# SATA-Modular-Backplane.net
KiCad netlist of a schematic drawn in Altium Designer
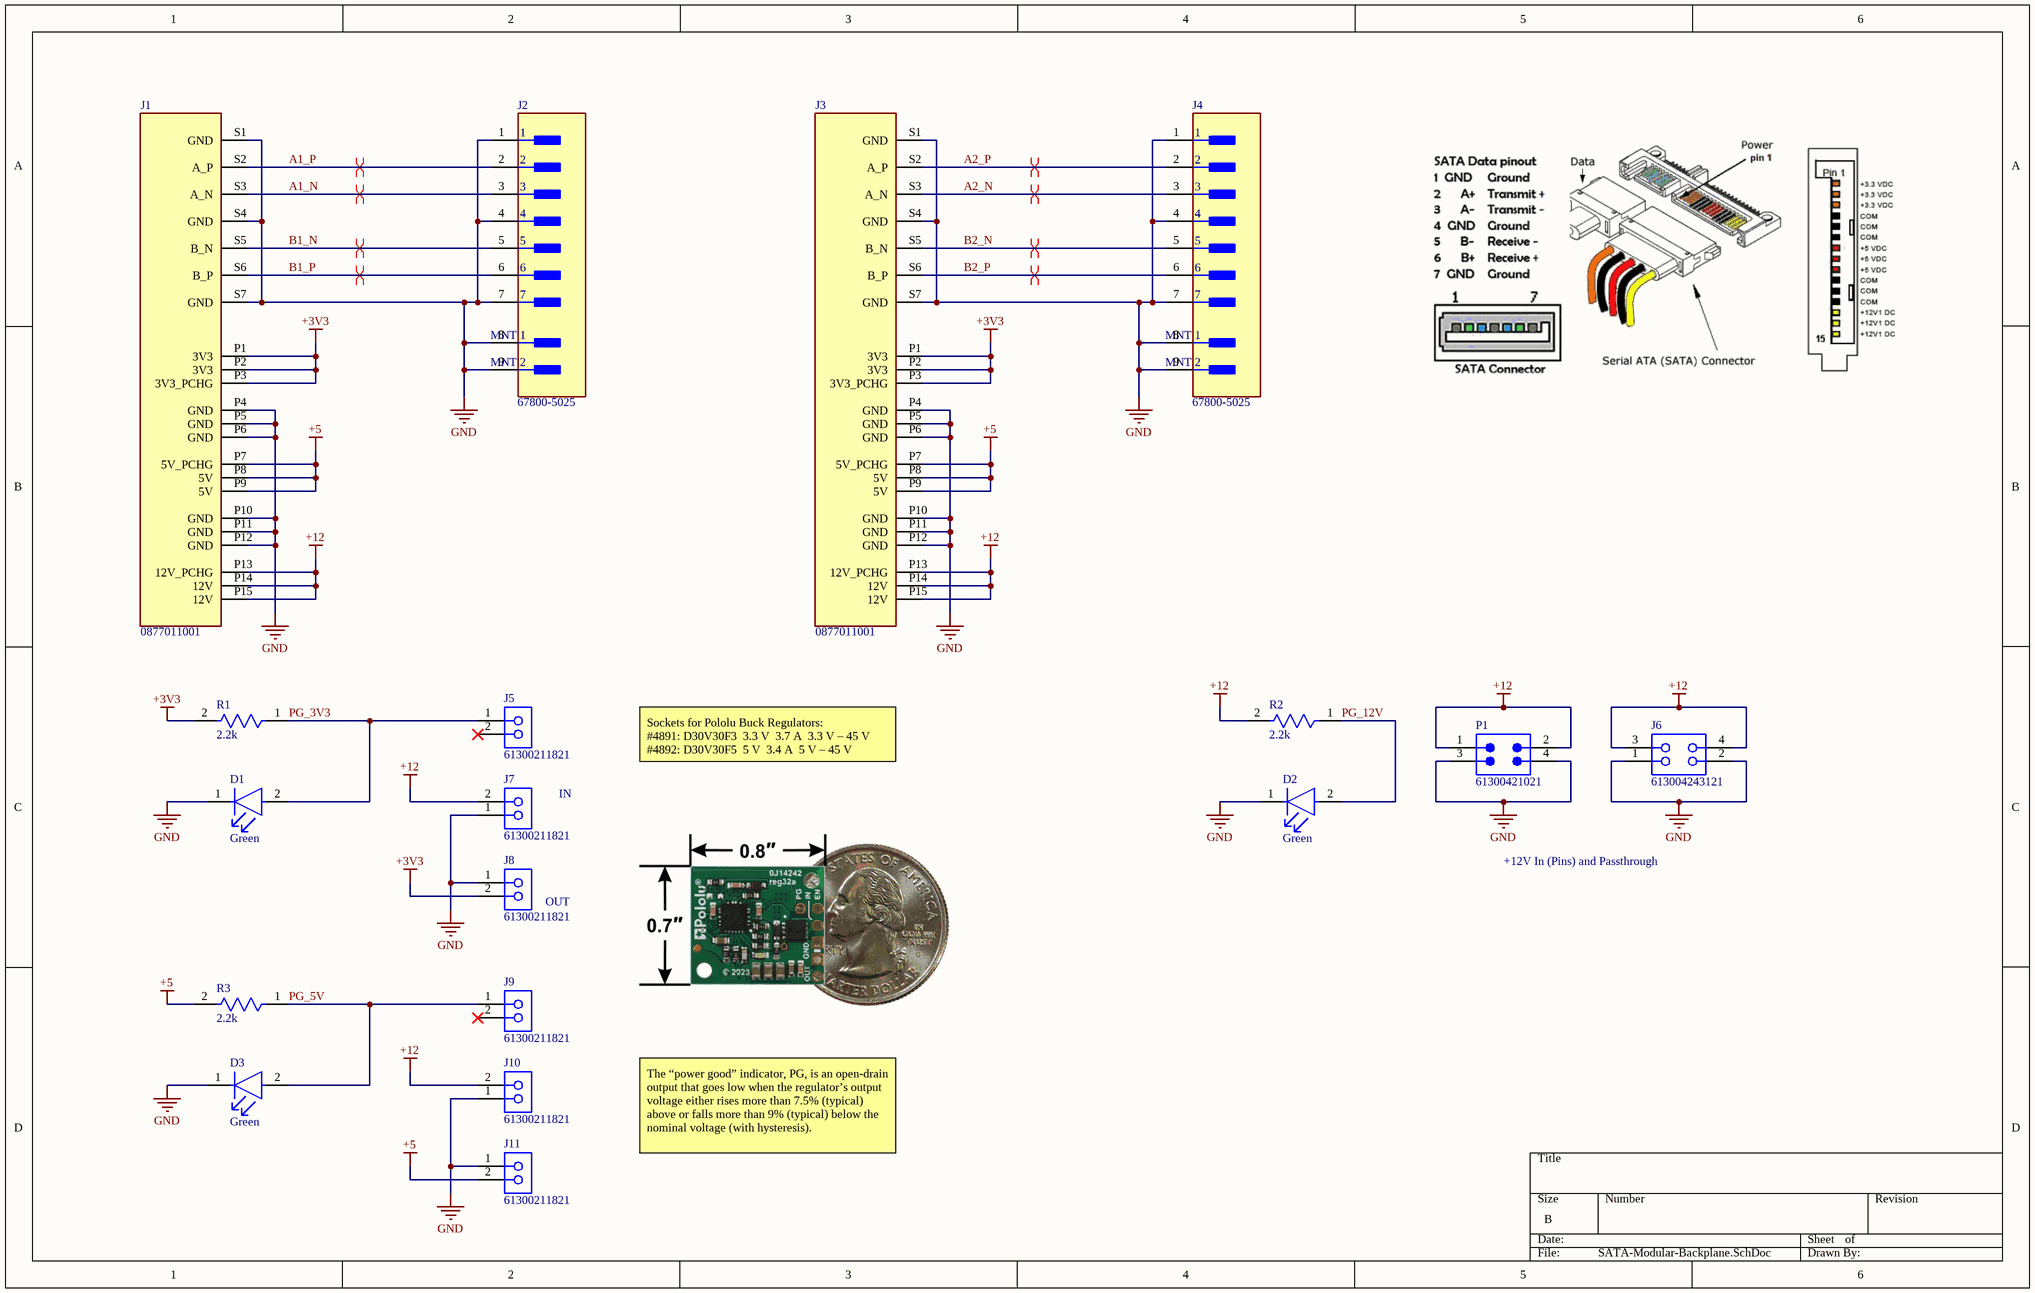
[diagram p0: SATA-Modular-Backplane.SchDoc]

(export (version "E")
  (design (tool "Eeschema 10.0.6"))
  (components
    (comp (ref "D1")
      (value "Green")
      (footprint "FP-LTST-C170GKT-MFG")
      (description "LED GREEN CLEAR SMD")
      (fields (field (name "VOLTAGE") "5V"))
      (libsource (lib "Altium Content Vault") (part "8706943c75ba83719d021d2fdc84c58"))
    )
    (comp (ref "D2")
      (value "Green")
      (footprint "FP-LTST-C170GKT-MFG")
      (description "LED GREEN CLEAR SMD")
      (fields (field (name "VOLTAGE") "5V"))
      (libsource (lib "Altium Content Vault") (part "8706943c75ba83719d021d2fdc84c58"))
    )
    (comp (ref "D3")
      (value "Green")
      (footprint "FP-LTST-C170GKT-MFG")
      (description "LED GREEN CLEAR SMD")
      (fields (field (name "VOLTAGE") "5V"))
      (libsource (lib "Altium Content Vault") (part "8706943c75ba83719d021d2fdc84c58"))
    )
    (comp (ref "J1")
      (value "0877011001")
      (footprint "SamacSys:0877011001")
      (description "I/O Connectors SATA COMBO HOST REC VT PFIT")
      (libsource (lib "Simple-Six-SATA-Backplane-Special") (part "0877011001"))
    )
    (comp (ref "J2")
      (value "67800-5025")
      (footprint "FP-67800-5025-MFG")
      (description "CONN SATA HEADER 7POS SLD SMD")
      (libsource (lib "Altium Content Vault") (part "989b0b90c267bc36b7e102b24762a7b"))
    )
    (comp (ref "J3")
      (value "0877011001")
      (footprint "SamacSys:0877011001")
      (description "I/O Connectors SATA COMBO HOST REC VT PFIT")
      (libsource (lib "Simple-Six-SATA-Backplane-Special") (part "0877011001"))
    )
    (comp (ref "J4")
      (value "67800-5025")
      (footprint "FP-67800-5025-MFG")
      (description "CONN SATA HEADER 7POS SLD SMD")
      (libsource (lib "Altium Content Vault") (part "989b0b90c267bc36b7e102b24762a7b"))
    )
    (comp (ref "J5")
      (value "61300211821")
      (footprint "61300211821")
      (libsource (lib "Altium Content Vault") (part "Header_Female_1R_02P"))
    )
    (comp (ref "J6")
      (value "613004243121")
      (footprint "613004243121")
      (libsource (lib "Altium Content Vault") (part "Header_Female_2R_04P"))
    )
    (comp (ref "J7")
      (value "61300211821")
      (footprint "61300211821")
      (libsource (lib "Altium Content Vault") (part "Header_Female_1R_02P"))
    )
    (comp (ref "J8")
      (value "61300211821")
      (footprint "61300211821")
      (libsource (lib "Altium Content Vault") (part "Header_Female_1R_02P"))
    )
    (comp (ref "J9")
      (value "61300211821")
      (footprint "61300211821")
      (libsource (lib "Altium Content Vault") (part "Header_Female_1R_02P"))
    )
    (comp (ref "J10")
      (value "61300211821")
      (footprint "61300211821")
      (libsource (lib "Altium Content Vault") (part "Header_Female_1R_02P"))
    )
    (comp (ref "J11")
      (value "61300211821")
      (footprint "61300211821")
      (libsource (lib "Altium Content Vault") (part "Header_Female_1R_02P"))
    )
    (comp (ref "P1")
      (value "61300421021")
      (footprint "61300421021")
      (libsource (lib "Altium Content Vault") (part "Header_Male_2R_04P"))
    )
    (comp (ref "R1")
      (value "2.2k")
      (footprint "FP-CRCW0805-e3-IPC_B")
      (description "RES Thick Film, 2.2kΩ, 1%, 0.125W, 100ppm/°C, 0805")
      (fields (field (name "TOLERANCE") "1%"))
      (libsource (lib "Altium Content Vault") (part "1029c3af85768c4190bb7ad29bc67b5"))
    )
    (comp (ref "R2")
      (value "2.2k")
      (footprint "FP-CRCW0805-e3-IPC_B")
      (description "RES Thick Film, 2.2kΩ, 1%, 0.125W, 100ppm/°C, 0805")
      (fields (field (name "TOLERANCE") "1%"))
      (libsource (lib "Altium Content Vault") (part "1029c3af85768c4190bb7ad29bc67b5"))
    )
    (comp (ref "R3")
      (value "2.2k")
      (footprint "FP-CRCW0805-e3-IPC_B")
      (description "RES Thick Film, 2.2kΩ, 1%, 0.125W, 100ppm/°C, 0805")
      (fields (field (name "TOLERANCE") "1%"))
      (libsource (lib "Altium Content Vault") (part "1029c3af85768c4190bb7ad29bc67b5"))
    )
  )
  (nets
    (net (code "1") (name "+3V3") (class "Default")
      (node (ref "J1") (pin "P1") (pinfunction "3V3_P1") (pintype "passive"))
      (node (ref "J1") (pin "P2") (pinfunction "3V3_P2") (pintype "passive"))
      (node (ref "J1") (pin "P3") (pinfunction "3V3_PCHG_P3") (pintype "passive"))
      (node (ref "J3") (pin "P1") (pinfunction "3V3_P1") (pintype "passive"))
      (node (ref "J3") (pin "P2") (pinfunction "3V3_P2") (pintype "passive"))
      (node (ref "J3") (pin "P3") (pinfunction "3V3_PCHG_P3") (pintype "passive"))
      (node (ref "J8") (pin "2") (pinfunction "2_2") (pintype "passive"))
      (node (ref "R1") (pin "2") (pinfunction "2_2") (pintype "passive"))
    )
    (net (code "2") (name "+5") (class "Default")
      (node (ref "J1") (pin "P7") (pinfunction "5V_PCHG_P7") (pintype "passive"))
      (node (ref "J1") (pin "P8") (pinfunction "5V_P8") (pintype "passive"))
      (node (ref "J1") (pin "P9") (pinfunction "5V_P9") (pintype "passive"))
      (node (ref "J11") (pin "2") (pinfunction "2_2") (pintype "passive"))
      (node (ref "J3") (pin "P7") (pinfunction "5V_PCHG_P7") (pintype "passive"))
      (node (ref "J3") (pin "P8") (pinfunction "5V_P8") (pintype "passive"))
      (node (ref "J3") (pin "P9") (pinfunction "5V_P9") (pintype "passive"))
      (node (ref "R3") (pin "2") (pinfunction "2_2") (pintype "passive"))
    )
    (net (code "3") (name "+12") (class "Default")
      (node (ref "J1") (pin "P13") (pinfunction "12V_PCHG_P13") (pintype "passive"))
      (node (ref "J1") (pin "P14") (pinfunction "12V_P14") (pintype "passive"))
      (node (ref "J1") (pin "P15") (pinfunction "12V_P15") (pintype "passive"))
      (node (ref "J10") (pin "2") (pinfunction "2_2") (pintype "passive"))
      (node (ref "J3") (pin "P13") (pinfunction "12V_PCHG_P13") (pintype "passive"))
      (node (ref "J3") (pin "P14") (pinfunction "12V_P14") (pintype "passive"))
      (node (ref "J3") (pin "P15") (pinfunction "12V_P15") (pintype "passive"))
      (node (ref "J6") (pin "3") (pinfunction "3_3") (pintype "passive"))
      (node (ref "J6") (pin "4") (pinfunction "4_4") (pintype "passive"))
      (node (ref "J7") (pin "2") (pinfunction "2_2") (pintype "passive"))
      (node (ref "P1") (pin "1") (pinfunction "1_1") (pintype "passive"))
      (node (ref "P1") (pin "2") (pinfunction "2_2") (pintype "passive"))
      (node (ref "R2") (pin "2") (pinfunction "2_2") (pintype "passive"))
    )
    (net (code "4") (name "/A1_N") (class "Default")
      (node (ref "J1") (pin "S3") (pinfunction "A_N_S3") (pintype "passive"))
      (node (ref "J2") (pin "3") (pinfunction "3_3") (pintype "passive"))
    )
    (net (code "5") (name "/A1_P") (class "Default")
      (node (ref "J1") (pin "S2") (pinfunction "A_P_S2") (pintype "passive"))
      (node (ref "J2") (pin "2") (pinfunction "2_2") (pintype "passive"))
    )
    (net (code "6") (name "/A2_N") (class "Default")
      (node (ref "J3") (pin "S3") (pinfunction "A_N_S3") (pintype "passive"))
      (node (ref "J4") (pin "3") (pinfunction "3_3") (pintype "passive"))
    )
    (net (code "7") (name "/A2_P") (class "Default")
      (node (ref "J3") (pin "S2") (pinfunction "A_P_S2") (pintype "passive"))
      (node (ref "J4") (pin "2") (pinfunction "2_2") (pintype "passive"))
    )
    (net (code "8") (name "/B1_N") (class "Default")
      (node (ref "J1") (pin "S5") (pinfunction "B_N_S5") (pintype "passive"))
      (node (ref "J2") (pin "5") (pinfunction "5_5") (pintype "passive"))
    )
    (net (code "9") (name "/B1_P") (class "Default")
      (node (ref "J1") (pin "S6") (pinfunction "B_P_S6") (pintype "passive"))
      (node (ref "J2") (pin "6") (pinfunction "6_6") (pintype "passive"))
    )
    (net (code "10") (name "/B2_N") (class "Default")
      (node (ref "J3") (pin "S5") (pinfunction "B_N_S5") (pintype "passive"))
      (node (ref "J4") (pin "5") (pinfunction "5_5") (pintype "passive"))
    )
    (net (code "11") (name "/B2_P") (class "Default")
      (node (ref "J3") (pin "S6") (pinfunction "B_P_S6") (pintype "passive"))
      (node (ref "J4") (pin "6") (pinfunction "6_6") (pintype "passive"))
    )
    (net (code "12") (name "/PG_3V3") (class "Default")
      (node (ref "D1") (pin "2") (pinfunction "A_2") (pintype "passive"))
      (node (ref "J5") (pin "1") (pinfunction "1_1") (pintype "passive"))
      (node (ref "R1") (pin "1") (pinfunction "1_1") (pintype "passive"))
    )
    (net (code "13") (name "/PG_5V") (class "Default")
      (node (ref "D3") (pin "2") (pinfunction "A_2") (pintype "passive"))
      (node (ref "J9") (pin "1") (pinfunction "1_1") (pintype "passive"))
      (node (ref "R3") (pin "1") (pinfunction "1_1") (pintype "passive"))
    )
    (net (code "14") (name "/PG_12V") (class "Default")
      (node (ref "D2") (pin "2") (pinfunction "A_2") (pintype "passive"))
      (node (ref "R2") (pin "1") (pinfunction "1_1") (pintype "passive"))
    )
    (net (code "15") (name "GND") (class "Default")
      (node (ref "D1") (pin "1") (pinfunction "C_1") (pintype "passive"))
      (node (ref "D2") (pin "1") (pinfunction "C_1") (pintype "passive"))
      (node (ref "D3") (pin "1") (pinfunction "C_1") (pintype "passive"))
      (node (ref "J1") (pin "P10") (pinfunction "GND_P10") (pintype "passive"))
      (node (ref "J1") (pin "P11") (pinfunction "GND_P11") (pintype "passive"))
      (node (ref "J1") (pin "P12") (pinfunction "GND_P12") (pintype "passive"))
      (node (ref "J1") (pin "P4") (pinfunction "GND_P4") (pintype "passive"))
      (node (ref "J1") (pin "P5") (pinfunction "GND_P5") (pintype "passive"))
      (node (ref "J1") (pin "P6") (pinfunction "GND_P6") (pintype "passive"))
      (node (ref "J1") (pin "S1") (pinfunction "GND_S1") (pintype "passive"))
      (node (ref "J1") (pin "S4") (pinfunction "GND_S4") (pintype "passive"))
      (node (ref "J1") (pin "S7") (pinfunction "GND_S7") (pintype "passive"))
      (node (ref "J10") (pin "1") (pinfunction "1_1") (pintype "passive"))
      (node (ref "J11") (pin "1") (pinfunction "1_1") (pintype "passive"))
      (node (ref "J2") (pin "1") (pinfunction "1_1") (pintype "passive"))
      (node (ref "J2") (pin "4") (pinfunction "4_4") (pintype "passive"))
      (node (ref "J2") (pin "7") (pinfunction "7_7") (pintype "passive"))
      (node (ref "J2") (pin "8") (pinfunction "MNT_1_8") (pintype "passive"))
      (node (ref "J2") (pin "9") (pinfunction "MNT_2_9") (pintype "passive"))
      (node (ref "J3") (pin "P10") (pinfunction "GND_P10") (pintype "passive"))
      (node (ref "J3") (pin "P11") (pinfunction "GND_P11") (pintype "passive"))
      (node (ref "J3") (pin "P12") (pinfunction "GND_P12") (pintype "passive"))
      (node (ref "J3") (pin "P4") (pinfunction "GND_P4") (pintype "passive"))
      (node (ref "J3") (pin "P5") (pinfunction "GND_P5") (pintype "passive"))
      (node (ref "J3") (pin "P6") (pinfunction "GND_P6") (pintype "passive"))
      (node (ref "J3") (pin "S1") (pinfunction "GND_S1") (pintype "passive"))
      (node (ref "J3") (pin "S4") (pinfunction "GND_S4") (pintype "passive"))
      (node (ref "J3") (pin "S7") (pinfunction "GND_S7") (pintype "passive"))
      (node (ref "J4") (pin "1") (pinfunction "1_1") (pintype "passive"))
      (node (ref "J4") (pin "4") (pinfunction "4_4") (pintype "passive"))
      (node (ref "J4") (pin "7") (pinfunction "7_7") (pintype "passive"))
      (node (ref "J4") (pin "8") (pinfunction "MNT_1_8") (pintype "passive"))
      (node (ref "J4") (pin "9") (pinfunction "MNT_2_9") (pintype "passive"))
      (node (ref "J6") (pin "1") (pinfunction "1_1") (pintype "passive"))
      (node (ref "J6") (pin "2") (pinfunction "2_2") (pintype "passive"))
      (node (ref "J7") (pin "1") (pinfunction "1_1") (pintype "passive"))
      (node (ref "J8") (pin "1") (pinfunction "1_1") (pintype "passive"))
      (node (ref "P1") (pin "3") (pinfunction "3_3") (pintype "passive"))
      (node (ref "P1") (pin "4") (pinfunction "4_4") (pintype "passive"))
    )
    (net (code "16") (name "unconnected-(J5-Pad2)") (class "Default")
      (node (ref "J5") (pin "2") (pinfunction "2_2") (pintype "passive+no_connect"))
    )
    (net (code "17") (name "unconnected-(J9-Pad2)") (class "Default")
      (node (ref "J9") (pin "2") (pinfunction "2_2") (pintype "passive+no_connect"))
    )
  )
)
